# CANTRICK_POWER.net
KiCad netlist of a schematic drawn in Altium Designer
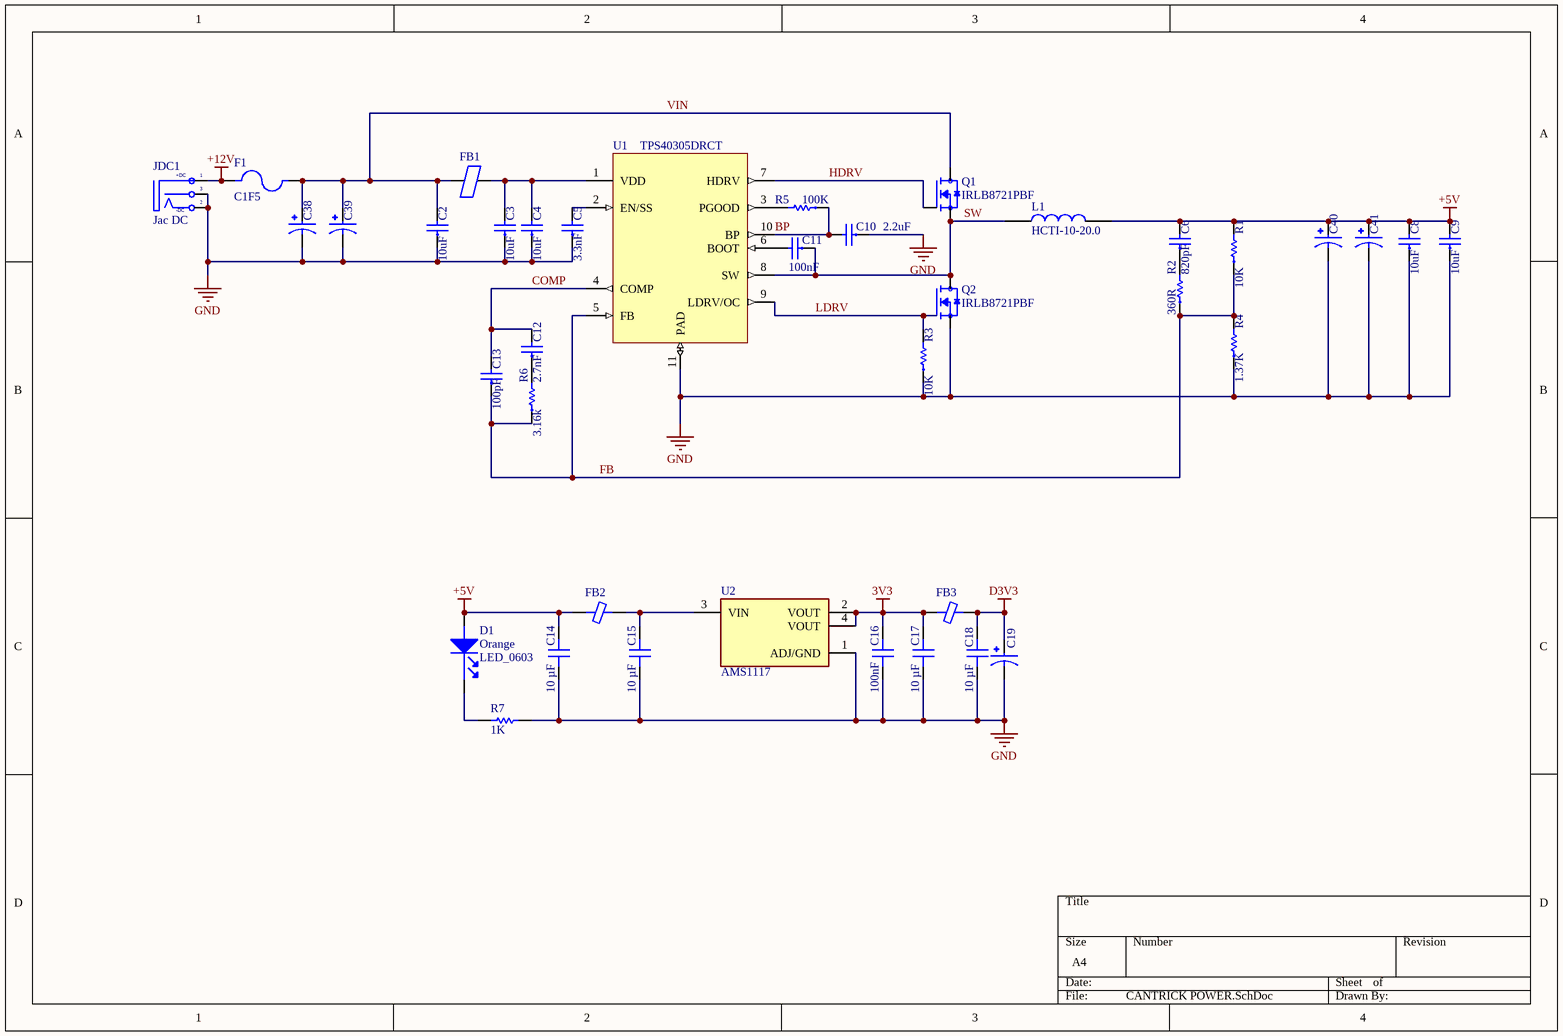
[diagram p0: CANTRICK POWER.SchDoc]

(export (version "E")
  (design (tool "Eeschema 10.0.6"))
  (components
    (comp (ref "C2")
      (value "10uF")
      (footprint "CAP-CER0603-0.8H")
      (description "CAP CER 100nF 10% 50V X7R 0603 SMD")
      (libsource (lib "NAVIGATION") (part "CAPCER0001 100nF 10% 50V X7R 0603 SMD"))
    )
    (comp (ref "C3")
      (value "10uF")
      (footprint "CAP-CER0603-0.8H")
      (description "CAP CER 100nF 10% 50V X7R 0603 SMD")
      (libsource (lib "NAVIGATION") (part "CAPCER0001 100nF 10% 50V X7R 0603 SMD"))
    )
    (comp (ref "C4")
      (value "10uF")
      (footprint "CAP-CER0603-0.8H")
      (description "CAP CER 100nF 10% 50V X7R 0603 SMD")
      (libsource (lib "NAVIGATION") (part "CAPCER0001 100nF 10% 50V X7R 0603 SMD"))
    )
    (comp (ref "C5")
      (value "3.3nF")
      (footprint "CAP-CER0603-0.8H")
      (description "CAP CER 100nF 10% 50V X7R 0603 SMD")
      (libsource (lib "NAVIGATION") (part "CAPCER0001 100nF 10% 50V X7R 0603 SMD"))
    )
    (comp (ref "C6")
      (value "820pF")
      (footprint "CAP-CER0603-0.8H")
      (description "CAP CER 100nF 10% 50V X7R 0603 SMD")
      (libsource (lib "NAVIGATION") (part "CAPCER0001 100nF 10% 50V X7R 0603 SMD"))
    )
    (comp (ref "C8")
      (value "10uF")
      (footprint "CAP-CER0603-0.8H")
      (description "CAP CER 100nF 10% 50V X7R 0603 SMD")
      (libsource (lib "NAVIGATION") (part "CAPCER0001 100nF 10% 50V X7R 0603 SMD"))
    )
    (comp (ref "C9")
      (value "10uF")
      (footprint "CAP-CER0603-0.8H")
      (description "CAP CER 100nF 10% 50V X7R 0603 SMD")
      (libsource (lib "NAVIGATION") (part "CAPCER0001 100nF 10% 50V X7R 0603 SMD"))
    )
    (comp (ref "C10")
      (value "2.2uF")
      (footprint "CAP-CER0603-0.8H")
      (description "CAP CER 100nF 10% 50V X7R 0603 SMD")
      (libsource (lib "NAVIGATION") (part "CAPCER0001 100nF 10% 50V X7R 0603 SMD"))
    )
    (comp (ref "C11")
      (value "100nF")
      (footprint "CAP-CER0603-0.8H")
      (description "CAP CER 100nF 10% 50V X7R 0603 SMD")
      (libsource (lib "NAVIGATION") (part "CAPCER0001 100nF 10% 50V X7R 0603 SMD"))
    )
    (comp (ref "C12")
      (value "2.7nF")
      (footprint "CAP-CER0603-0.8H")
      (description "CAP CER 100nF 10% 50V X7R 0603 SMD")
      (libsource (lib "NAVIGATION") (part "CAPCER0001 100nF 10% 50V X7R 0603 SMD"))
    )
    (comp (ref "C13")
      (value "100pF")
      (footprint "CAP-CER0603-0.8H")
      (description "CAP CER 100nF 10% 50V X7R 0603 SMD")
      (libsource (lib "NAVIGATION") (part "CAPCER0001 100nF 10% 50V X7R 0603 SMD"))
    )
    (comp (ref "C14")
      (value "10 µF")
      (footprint "CAP 0603")
      (description "CAP0603 X7R 10UF 10% 10V")
      (fields
        (field (name "PART NUMBER") "GMC10X7R106K10NT")
        (field (name "MANUFACTURER") "Cal-Chip Electronics, Inc.")
      )
      (libsource (lib "Celestial Altium Library - altium_library") (part "Capacitor"))
    )
    (comp (ref "C15")
      (value "10 µF")
      (footprint "CAP 0603")
      (description "CAP0603 X7R 10UF 10% 10V")
      (fields
        (field (name "PART NUMBER") "GMC10X7R106K10NT")
        (field (name "MANUFACTURER") "Cal-Chip Electronics, Inc.")
      )
      (libsource (lib "Celestial Altium Library - altium_library") (part "Capacitor"))
    )
    (comp (ref "C16")
      (value "100nF")
      (footprint "CAP 0603")
      (description "CAP0603 X7R 10UF 10% 10V")
      (fields
        (field (name "PART NUMBER") "GMC10X7R106K10NT")
        (field (name "MANUFACTURER") "Cal-Chip Electronics, Inc.")
      )
      (libsource (lib "Celestial Altium Library - altium_library") (part "Capacitor"))
    )
    (comp (ref "C17")
      (value "10 µF")
      (footprint "CAP 0603")
      (description "CAP0603 X7R 10UF 10% 10V")
      (fields
        (field (name "PART NUMBER") "GMC10X7R106K10NT")
        (field (name "MANUFACTURER") "Cal-Chip Electronics, Inc.")
      )
      (libsource (lib "Celestial Altium Library - altium_library") (part "Capacitor"))
    )
    (comp (ref "C18")
      (value "10 µF")
      (footprint "CAP 0603")
      (description "CAP0603 X7R 10UF 10% 10V")
      (fields
        (field (name "PART NUMBER") "GMC10X7R106K10NT")
        (field (name "MANUFACTURER") "Cal-Chip Electronics, Inc.")
      )
      (libsource (lib "Celestial Altium Library - altium_library") (part "Capacitor"))
    )
    (comp (ref "C19")
      (value "ECA1CHG331")
      (footprint "330UF-5mm")
      (fields (field (name "MP") "ECA-1CHG331") (field (name "MF") "Panasonic"))
      (libsource (lib "ECA1CHG331") (part "ECA1CHG331"))
    )
    (comp (ref "C38")
      (value "EEUFC1V222")
      (footprint "CAPPRD750W80D1600H3150")
      (description "2200ÂµF 35V Aluminum Electrolytic Capacitors Radial, Can 5000 Hrs @ 105Â°C")
      (fields (field (name "MF") "Panasonic"))
      (libsource (lib "EEUFC1V222") (part "EEUFC1V222"))
    )
    (comp (ref "C39")
      (value "EEUFC1V222")
      (footprint "CAPPRD750W80D1600H3150")
      (description "2200ÂµF 35V Aluminum Electrolytic Capacitors Radial, Can 5000 Hrs @ 105Â°C")
      (fields (field (name "MF") "Panasonic"))
      (libsource (lib "EEUFC1V222") (part "EEUFC1V222"))
    )
    (comp (ref "C40")
      (value "EEUFC1V222")
      (footprint "CAPPRD750W80D1600H3150")
      (description "2200ÂµF 35V Aluminum Electrolytic Capacitors Radial, Can 5000 Hrs @ 105Â°C")
      (fields (field (name "MF") "Panasonic"))
      (libsource (lib "EEUFC1V222") (part "EEUFC1V222"))
    )
    (comp (ref "C41")
      (value "EEUFC1V222")
      (footprint "CAPPRD750W80D1600H3150")
      (description "2200ÂµF 35V Aluminum Electrolytic Capacitors Radial, Can 5000 Hrs @ 105Â°C")
      (fields (field (name "MF") "Panasonic"))
      (libsource (lib "EEUFC1V222") (part "EEUFC1V222"))
    )
    (comp (ref "D1")
      (value "Orange")
      (footprint "LED")
      (description "LED SMARTLED ORANGE 606NM 0603")
      (fields
        (field (name "MANUFACTURER") "OSRAM Opto Semiconductors Inc")
        (field (name "MANUFACTURER PART NUMBER") "LO L29K-H2K1-24-Z")
        (field (name "PACKAGE / CASE") "LED_0603")
        (field (name "BY") "Hieu.Nguyen_20191030")
      )
      (libsource (lib "Stm32_Flyback_Driver_250814_1") (part "LED ORANGE 606NM 0603"))
    )
    (comp (ref "F1")
      (value "C1F5")
      (footprint "FUSE C1F5")
      (description "Fuse Chip Fast Acting 5A 125V SMD Solder Pad 1206 3.2 X 1.58 X 0.63mm")
      (fields (field (name "MANUFACTURER") "Bel TRP"))
      (libsource (lib "POWER_PIN_CAMERA") (part "C1F5"))
    )
    (comp (ref "FB1")
      (value "100MHz 2A 50mOhm")
      (footprint "FB 0603")
      (description "Ferrite Beads Multi-Layer 120Ohm 25% 100MHz 2A 50mOhm DCR 0603 Paper T/R")
      (fields
        (field (name "MANUFACTURER") "Murata")
        (field (name "MANUFACTURER PART NUMBER") "BLM18PG121SN1D")
      )
      (libsource (lib "POWER_PIN_CAMERA") (part "BLM18PG121SN1D"))
    )
    (comp (ref "FB2")
      (value "330 Ohms @ 100 MHz")
      (footprint "FB_0603")
      (description "FERRITE BEAD 330 OHM 0603 1LN")
      (fields
        (field (name "PART NUMBER") "BLM18KG331SH1D")
        (field (name "MANUFACTURER") "Murata Electronics")
      )
      (libsource (lib "Celestial Altium Library - altium_library") (part "Ferrite Chip"))
    )
    (comp (ref "FB3")
      (value "330 Ohms @ 100 MHz")
      (footprint "FB_0603")
      (description "FERRITE BEAD 330 OHM 0603 1LN")
      (fields
        (field (name "PART NUMBER") "BLM18KG331SH1D")
        (field (name "MANUFACTURER") "Murata Electronics")
      )
      (libsource (lib "Celestial Altium Library - altium_library") (part "Ferrite Chip"))
    )
    (comp (ref "JDC1")
      (value "Jac DC")
      (footprint "DC0")
      (description "Jac DC input")
      (libsource (lib "2502-GMQLITE-MAIN") (part "DCIN"))
    )
    (comp (ref "L1")
      (value "HCTI-10-20.0")
      (footprint "IND_HCTI-10-20.0")
      (description "High Current Toroidal Inductor ¦ 10 uH")
      (fields (field (name "MF") "Signal Transformer"))
      (libsource (lib "HCTI-10-20.0") (part "HCTI-10-20.0"))
    )
    (comp (ref "Q1")
      (value "IRLB8721PBF")
      (footprint "TO254P1067X483X2057-3")
      (description "IRLB8721PBF N-channel MOSFET Transistor, 62 A, 30 V, 3-Pin TO-220AB ¦ Infineon IRLB8721PBF")
      (fields (field (name "MF") "Infineon Technologies"))
      (libsource (lib "NAVIGATION") (part "IRLB8721PBF"))
    )
    (comp (ref "Q2")
      (value "IRLB8721PBF")
      (footprint "TO254P1067X483X2057-3")
      (description "IRLB8721PBF N-channel MOSFET Transistor, 62 A, 30 V, 3-Pin TO-220AB ¦ Infineon IRLB8721PBF")
      (fields (field (name "MF") "Infineon Technologies"))
      (libsource (lib "NAVIGATION") (part "IRLB8721PBF"))
    )
    (comp (ref "R1")
      (value "10K")
      (footprint "RES-CHP0603-0.45H-101")
      (description "RES CHP 165K 1% 1/10W 0603 SMD")
      (libsource (lib "2502-GMQLITE-MAIN") (part "RESCHP0427 165K 1% 0603 SMD"))
    )
    (comp (ref "R2")
      (value "360R")
      (footprint "RES-CHP0603-0.45H-101")
      (description "RES CHP 165K 1% 1/10W 0603 SMD")
      (libsource (lib "2502-GMQLITE-MAIN") (part "RESCHP0427 165K 1% 0603 SMD"))
    )
    (comp (ref "R3")
      (value "10K")
      (footprint "RES-CHP0603-0.45H-101")
      (description "RES CHP 165K 1% 1/10W 0603 SMD")
      (libsource (lib "2502-GMQLITE-MAIN") (part "RESCHP0427 165K 1% 0603 SMD"))
    )
    (comp (ref "R4")
      (value "1.37K")
      (footprint "RES-CHP0603-0.45H-101")
      (description "RES CHP 165K 1% 1/10W 0603 SMD")
      (libsource (lib "2502-GMQLITE-MAIN") (part "RESCHP0427 165K 1% 0603 SMD"))
    )
    (comp (ref "R5")
      (value "100K")
      (footprint "RES-CHP0603-0.45H-101")
      (description "RES CHP 165K 1% 1/10W 0603 SMD")
      (libsource (lib "2502-GMQLITE-MAIN") (part "RESCHP0427 165K 1% 0603 SMD"))
    )
    (comp (ref "R6")
      (value "3.16k")
      (footprint "RES-CHP0603-0.45H-101")
      (description "RES CHP 165K 1% 1/10W 0603 SMD")
      (libsource (lib "2502-GMQLITE-MAIN") (part "RESCHP0427 165K 1% 0603 SMD"))
    )
    (comp (ref "R7")
      (value "1K")
      (footprint "Res 0603")
      (description "Res Thick Film 0603 2.2K Ohm 5% 1/10W ±200ppm/°C Molded SMD SMD Paper T/R")
      (fields
        (field (name "MANUFACTURER") "Vishay")
        (field (name "MANUFACTURER PART NUMBER") "CRCW06032K20JNEA")
      )
      (libsource (lib "Stm32_Flyback_Driver_250814_1") (part "Resistor 2.2K"))
    )
    (comp (ref "U1")
      (value "TPS40305DRCT")
      (footprint "VREG_V62/16624-01YE")
      (description "3-V to 20-V, 25-A, 1.2-MHz synchronous buck controller with FSS")
      (fields (field (name "MF") "Texas Instruments"))
      (libsource (lib "TPS40305DRCT") (part "TPS40305DRCT"))
    )
    (comp (ref "U2")
      (value "AMS1117")
      (footprint "AMS1117")
      (description "1A LOW DROPOUT VOLTAGE REGULATOR SOT-223")
      (fields (field (name "MF") "Advanced Monolithic Systems"))
      (libsource (lib "AMS1117") (part "AMS1117"))
    )
  )
  (nets
    (net (code "1") (name "+5V") (class "Default")
      (node (ref "C14") (pin "2") (pinfunction "2_2") (pintype "passive"))
      (node (ref "C40") (pin "P") (pinfunction "P_P") (pintype "passive"))
      (node (ref "C41") (pin "P") (pinfunction "P_P") (pintype "passive"))
      (node (ref "C6") (pin "2") (pinfunction "2_2") (pintype "passive"))
      (node (ref "C8") (pin "2") (pinfunction "2_2") (pintype "passive"))
      (node (ref "C9") (pin "2") (pinfunction "2_2") (pintype "passive"))
      (node (ref "D1") (pin "1") (pinfunction "ANODE_1") (pintype "passive"))
      (node (ref "FB2") (pin "1") (pinfunction "1_1") (pintype "passive"))
      (node (ref "L1") (pin "2") (pinfunction "2_2") (pintype "passive"))
      (node (ref "R1") (pin "2") (pinfunction "2_2") (pintype "passive"))
    )
    (net (code "2") (name "+12V") (class "Default")
      (node (ref "F1") (pin "1") (pinfunction "1_1") (pintype "passive"))
      (node (ref "JDC1") (pin "1") (pinfunction "T_1") (pintype "passive"))
    )
    (net (code "3") (name "/BP") (class "Default")
      (node (ref "C10") (pin "2") (pinfunction "2_2") (pintype "passive"))
      (node (ref "R5") (pin "1") (pinfunction "1_1") (pintype "passive"))
      (node (ref "U1") (pin "10") (pinfunction "BP_10") (pintype "output"))
    )
    (net (code "4") (name "/COMP") (class "Default")
      (node (ref "C12") (pin "2") (pinfunction "2_2") (pintype "passive"))
      (node (ref "C13") (pin "2") (pinfunction "2_2") (pintype "passive"))
      (node (ref "U1") (pin "4") (pinfunction "COMP_4") (pintype "output"))
    )
    (net (code "5") (name "/FB") (class "Default")
      (node (ref "C13") (pin "1") (pinfunction "1_1") (pintype "passive"))
      (node (ref "R1") (pin "1") (pinfunction "1_1") (pintype "passive"))
      (node (ref "R2") (pin "1") (pinfunction "1_1") (pintype "passive"))
      (node (ref "R4") (pin "2") (pinfunction "2_2") (pintype "passive"))
      (node (ref "R6") (pin "1") (pinfunction "1_1") (pintype "passive"))
      (node (ref "U1") (pin "5") (pinfunction "FB_5") (pintype "input"))
    )
    (net (code "6") (name "/HDRV") (class "Default")
      (node (ref "Q1") (pin "1") (pinfunction "G_1") (pintype "passive"))
      (node (ref "U1") (pin "7") (pinfunction "HDRV_7") (pintype "output"))
    )
    (net (code "7") (name "/LDRV") (class "Default")
      (node (ref "Q2") (pin "1") (pinfunction "G_1") (pintype "passive"))
      (node (ref "R3") (pin "2") (pinfunction "2_2") (pintype "passive"))
      (node (ref "U1") (pin "9") (pinfunction "LDRV/OC_9") (pintype "output"))
    )
    (net (code "8") (name "/SW") (class "Default")
      (node (ref "C11") (pin "1") (pinfunction "1_1") (pintype "passive"))
      (node (ref "L1") (pin "1") (pinfunction "1_1") (pintype "passive"))
      (node (ref "Q1") (pin "3") (pinfunction "S_3") (pintype "passive"))
      (node (ref "Q2") (pin "2") (pinfunction "D_2") (pintype "passive"))
      (node (ref "U1") (pin "8") (pinfunction "SW_8") (pintype "output"))
    )
    (net (code "9") (name "/VIN") (class "Default")
      (node (ref "C2") (pin "2") (pinfunction "2_2") (pintype "passive"))
      (node (ref "C38") (pin "P") (pinfunction "P_P") (pintype "passive"))
      (node (ref "C39") (pin "P") (pinfunction "P_P") (pintype "passive"))
      (node (ref "F1") (pin "2") (pinfunction "2_2") (pintype "passive"))
      (node (ref "FB1") (pin "1") (pinfunction "1_1") (pintype "passive"))
      (node (ref "Q1") (pin "2") (pinfunction "D_2") (pintype "passive"))
    )
    (net (code "10") (name "3V3") (class "Default")
      (node (ref "C16") (pin "2") (pinfunction "2_2") (pintype "passive"))
      (node (ref "C17") (pin "2") (pinfunction "2_2") (pintype "passive"))
      (node (ref "FB3") (pin "1") (pinfunction "1_1") (pintype "passive"))
      (node (ref "U2") (pin "2") (pinfunction "VOUT_2") (pintype "passive"))
      (node (ref "U2") (pin "4") (pinfunction "VOUT_4") (pintype "passive"))
    )
    (net (code "11") (name "D3V3") (class "Default")
      (node (ref "C18") (pin "2") (pinfunction "2_2") (pintype "passive"))
      (node (ref "C19") (pin "1") (pinfunction "1_1") (pintype "passive"))
      (node (ref "FB3") (pin "2") (pinfunction "2_2") (pintype "passive"))
    )
    (net (code "12") (name "GND") (class "Default")
      (node (ref "C10") (pin "1") (pinfunction "1_1") (pintype "passive"))
      (node (ref "C14") (pin "1") (pinfunction "1_1") (pintype "passive"))
      (node (ref "C15") (pin "1") (pinfunction "1_1") (pintype "passive"))
      (node (ref "C16") (pin "1") (pinfunction "1_1") (pintype "passive"))
      (node (ref "C17") (pin "1") (pinfunction "1_1") (pintype "passive"))
      (node (ref "C18") (pin "1") (pinfunction "1_1") (pintype "passive"))
      (node (ref "C19") (pin "2") (pinfunction "2_2") (pintype "passive"))
      (node (ref "C2") (pin "1") (pinfunction "1_1") (pintype "passive"))
      (node (ref "C3") (pin "1") (pinfunction "1_1") (pintype "passive"))
      (node (ref "C38") (pin "N") (pinfunction "N_N") (pintype "passive"))
      (node (ref "C39") (pin "N") (pinfunction "N_N") (pintype "passive"))
      (node (ref "C4") (pin "1") (pinfunction "1_1") (pintype "passive"))
      (node (ref "C40") (pin "N") (pinfunction "N_N") (pintype "passive"))
      (node (ref "C41") (pin "N") (pinfunction "N_N") (pintype "passive"))
      (node (ref "C5") (pin "1") (pinfunction "1_1") (pintype "passive"))
      (node (ref "C8") (pin "1") (pinfunction "1_1") (pintype "passive"))
      (node (ref "C9") (pin "1") (pinfunction "1_1") (pintype "passive"))
      (node (ref "JDC1") (pin "2") (pinfunction "TN_2") (pintype "passive"))
      (node (ref "JDC1") (pin "3") (pinfunction "S_3") (pintype "power_in"))
      (node (ref "Q2") (pin "3") (pinfunction "S_3") (pintype "passive"))
      (node (ref "R3") (pin "1") (pinfunction "1_1") (pintype "passive"))
      (node (ref "R4") (pin "1") (pinfunction "1_1") (pintype "passive"))
      (node (ref "R7") (pin "2") (pinfunction "2_2") (pintype "passive"))
      (node (ref "U1") (pin "11") (pinfunction "PAD_11") (pintype "bidirectional"))
      (node (ref "U2") (pin "1") (pinfunction "ADJ/GND_1") (pintype "power_in"))
    )
    (net (code "13") (name "Net-(C6-Pad1)") (class "Default")
      (node (ref "C6") (pin "1") (pinfunction "1_1") (pintype "passive"))
      (node (ref "R2") (pin "2") (pinfunction "2_2") (pintype "passive"))
    )
    (net (code "14") (name "Net-(C12-Pad1)") (class "Default")
      (node (ref "C12") (pin "1") (pinfunction "1_1") (pintype "passive"))
      (node (ref "R6") (pin "2") (pinfunction "2_2") (pintype "passive"))
    )
    (net (code "15") (name "Net-(D1-cathode)") (class "Default")
      (node (ref "D1") (pin "2") (pinfunction "cathode_2") (pintype "passive"))
      (node (ref "R7") (pin "1") (pinfunction "1_1") (pintype "passive"))
    )
    (net (code "16") (name "Net-(U1-BOOT)") (class "Default")
      (node (ref "C11") (pin "2") (pinfunction "2_2") (pintype "passive"))
      (node (ref "U1") (pin "6") (pinfunction "BOOT_6") (pintype "input"))
    )
    (net (code "17") (name "Net-(U1-EN{slash}SS)") (class "Default")
      (node (ref "C5") (pin "2") (pinfunction "2_2") (pintype "passive"))
      (node (ref "U1") (pin "2") (pinfunction "EN/SS_2") (pintype "input"))
    )
    (net (code "18") (name "Net-(U1-PGOOD)") (class "Default")
      (node (ref "R5") (pin "2") (pinfunction "2_2") (pintype "passive"))
      (node (ref "U1") (pin "3") (pinfunction "PGOOD_3") (pintype "output"))
    )
    (net (code "19") (name "Net-(U1-VDD)") (class "Default")
      (node (ref "C3") (pin "2") (pinfunction "2_2") (pintype "passive"))
      (node (ref "C4") (pin "2") (pinfunction "2_2") (pintype "passive"))
      (node (ref "FB1") (pin "2") (pinfunction "2_2") (pintype "passive"))
      (node (ref "U1") (pin "1") (pinfunction "VDD_1") (pintype "power_in"))
    )
    (net (code "20") (name "Net-(U2-VIN)") (class "Default")
      (node (ref "C15") (pin "2") (pinfunction "2_2") (pintype "passive"))
      (node (ref "FB2") (pin "2") (pinfunction "2_2") (pintype "passive"))
      (node (ref "U2") (pin "3") (pinfunction "VIN_3") (pintype "passive"))
    )
  )
)
